# Regulator.net
KiCad netlist of a schematic drawn in Altium Designer
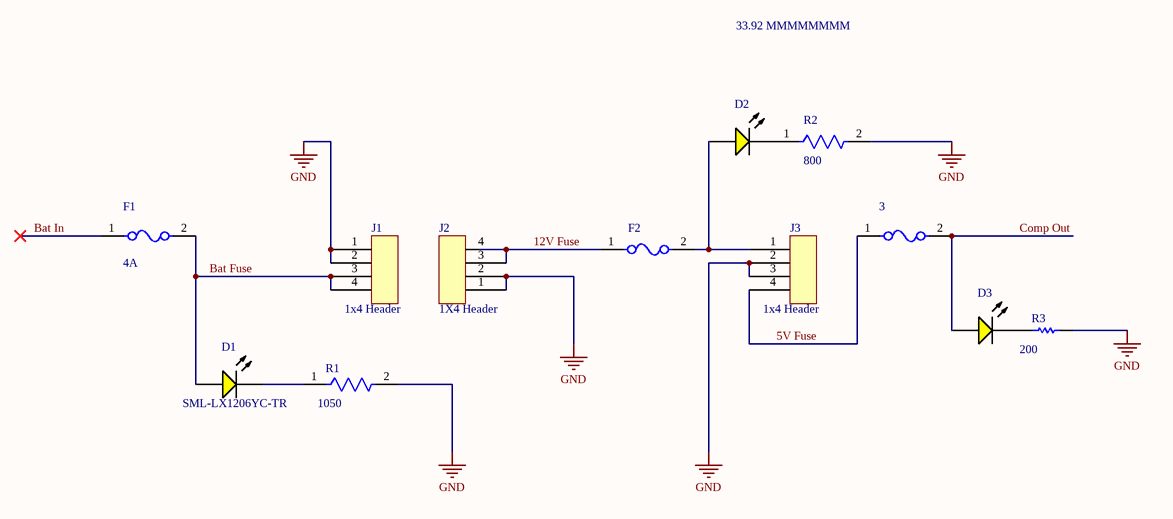
[diagram p0: Regulator.SchDoc]

(export (version "E")
  (design (tool "Eeschema 10.0.6"))
  (components
    (comp (ref "3")
      (value "5A")
      (footprint "FP-0469-MFG")
      (description "FUSE BOARD MOUNT 5A 32VDC 1206")
      (libsource (lib "Altium Content Vault") (part "5bcf9b9f640e542cf0359d10258e979"))
    )
    (comp (ref "D1")
      (value "SML-LX1206YC-TR")
      (footprint "LUMX-SML-LX1206YC-TR_V")
      (description "Yellow LED, Water Clear Len, 585 nm, 2.1 V, -40 to 85 degC, 2-Pin SMD, RoHS, Tape and Reel")
      (fields (field (name "MANUFACTURER") "Lumex"))
      (libsource (lib "Altium Content Vault") (part "LED-YELLOW-AK-2"))
    )
    (comp (ref "D2")
      (value "SML-LX1206YC-TR")
      (footprint "LUMX-SML-LX1206YC-TR_V")
      (description "Yellow LED, Water Clear Len, 585 nm, 2.1 V, -40 to 85 degC, 2-Pin SMD, RoHS, Tape and Reel")
      (fields (field (name "MANUFACTURER") "Lumex"))
      (libsource (lib "Altium Content Vault") (part "LED-YELLOW-AK-2"))
    )
    (comp (ref "D3")
      (value "SML-LX1206YC-TR")
      (footprint "LUMX-SML-LX1206YC-TR_V")
      (description "Yellow LED, Water Clear Len, 585 nm, 2.1 V, -40 to 85 degC, 2-Pin SMD, RoHS, Tape and Reel")
      (fields (field (name "MANUFACTURER") "Lumex"))
      (libsource (lib "Altium Content Vault") (part "LED-YELLOW-AK-2"))
    )
    (comp (ref "F1")
      (value "4A")
      (footprint "FP-0685T-IPC_B")
      (description "4A 63V AC 63V DC Fuse Board Mount (Cartridge Style Excluded) Surface Mount 1206 (3216 Metric)")
      (libsource (lib "Altium Content Vault") (part "5bcf9b9f640e542cf0359d10258e979"))
    )
    (comp (ref "F2")
      (value "3A")
      (footprint "FP-0466-MFG")
      (description "FUSE BOARD MNT 3A 32VAC/VDC 1206")
      (fields
        (field (name "OCTOPART") "https://octopart.com/0466003.nr-littelfuse-565175")
        (field (name "MANUFACTURER PART NUMBER") "0466003.NR")
      )
      (libsource (lib "Altium Content Vault") (part "5bcf9b9f640e542cf0359d10258e979"))
    )
    (comp (ref "J1")
      (value "1x4 Header")
      (footprint "1X4 HEADER")
      (description "CONN HEADER VERT 4POS 2.54MM")
      (fields
        (field (name "MANUFACTURER") "Würth Elektronik")
        (field (name "MANUFACTURER PART NUMBER") "61300411121")
      )
      (libsource (lib "URC_Lib") (part "1X4 Header"))
    )
    (comp (ref "J2")
      (value "1X4 Header")
      (footprint "1X4 HEADER")
      (description "CONN HEADER VERT 4POS 2.54MM")
      (fields
        (field (name "MANUFACTURER") "Würth Elektronik")
        (field (name "MANUFACTURER PART NUMBER") "61300411121")
      )
      (libsource (lib "") (part "1X4 Header_1"))
    )
    (comp (ref "J3")
      (value "1x4 Header")
      (footprint "1X4 HEADER")
      (description "CONN HEADER VERT 4POS 2.54MM")
      (fields
        (field (name "MANUFACTURER") "Würth Elektronik")
        (field (name "MANUFACTURER PART NUMBER") "61300411121")
      )
      (libsource (lib "URC_Lib") (part "1X4 Header"))
    )
    (comp (ref "R1")
      (value "1050")
      (footprint "FP-CR1206-IPC_B")
      (description "Thick Film Chip Resistors 1206 1.05kΩ 0.25W 1% 100ppm/°C")
      (fields (field (name "TOLERANCE") "1%"))
      (libsource (lib "Altium Content Vault") (part "1029c3af85768c4190bb7ad29bc67b5"))
    )
    (comp (ref "R2")
      (value "800")
      (footprint "FP-MCA1206-IPC_C")
      (description "Res MC Precision Thin Film 1206 800Ω 0.1% 0.25W ±25ppm/°C Molded Paper T/R")
      (fields (field (name "TOLERANCE") "0.1%"))
      (libsource (lib "Altium Content Vault") (part "1029c3af85768c4190bb7ad29bc67b5"))
    )
    (comp (ref "R3")
      (value "200")
      (footprint "RESC3216X70X50LL05T20")
      (fields (field (name "PART NUMBER") "ERJ-8GEYJ201V") (field (name "MANUFACTURER") "Panasonic"))
      (libsource (lib "Altium Content Vault") (part "RES"))
    )
  )
  (nets
    (net (code "1") (name "/5V Fuse") (class "Default")
      (node (ref "3") (pin "1") (pinfunction "1_1") (pintype "passive"))
      (node (ref "J3") (pin "4") (pinfunction "4_4") (pintype "passive"))
    )
    (net (code "2") (name "/12V Fuse") (class "Default")
      (node (ref "F2") (pin "1") (pinfunction "1_1") (pintype "passive"))
      (node (ref "J2") (pin "3") (pinfunction "3_3") (pintype "passive"))
      (node (ref "J2") (pin "4") (pinfunction "4_4") (pintype "passive"))
    )
    (net (code "3") (name "/Bat Fuse") (class "Default")
      (node (ref "D1") (pin "1") (pinfunction "A_1") (pintype "passive"))
      (node (ref "F1") (pin "2") (pinfunction "2_2") (pintype "passive"))
      (node (ref "J1") (pin "3") (pinfunction "3_3") (pintype "passive"))
      (node (ref "J1") (pin "4") (pinfunction "4_4") (pintype "passive"))
    )
    (net (code "4") (name "/Bat In") (class "Default")
      (node (ref "F1") (pin "1") (pinfunction "1_1") (pintype "passive+no_connect"))
    )
    (net (code "5") (name "/Comp Out") (class "Default")
      (node (ref "3") (pin "2") (pinfunction "2_2") (pintype "passive"))
      (node (ref "D3") (pin "1") (pinfunction "A_1") (pintype "passive"))
    )
    (net (code "6") (name "GND") (class "Default")
      (node (ref "J1") (pin "1") (pinfunction "1_1") (pintype "passive"))
      (node (ref "J1") (pin "2") (pinfunction "2_2") (pintype "passive"))
      (node (ref "J2") (pin "1") (pinfunction "1_1") (pintype "passive"))
      (node (ref "J2") (pin "2") (pinfunction "2_2") (pintype "passive"))
      (node (ref "J3") (pin "2") (pinfunction "2_2") (pintype "passive"))
      (node (ref "J3") (pin "3") (pinfunction "3_3") (pintype "passive"))
      (node (ref "R1") (pin "2") (pinfunction "2_2") (pintype "passive"))
      (node (ref "R2") (pin "2") (pinfunction "2_2") (pintype "passive"))
      (node (ref "R3") (pin "2") (pinfunction "2_2") (pintype "passive"))
    )
    (net (code "7") (name "Net-(D1-K)") (class "Default")
      (node (ref "D1") (pin "2") (pinfunction "K_2") (pintype "passive"))
      (node (ref "R1") (pin "1") (pinfunction "1_1") (pintype "passive"))
    )
    (net (code "8") (name "Net-(D2-A)") (class "Default")
      (node (ref "D2") (pin "1") (pinfunction "A_1") (pintype "passive"))
      (node (ref "F2") (pin "2") (pinfunction "2_2") (pintype "passive"))
      (node (ref "J3") (pin "1") (pinfunction "1_1") (pintype "passive"))
    )
    (net (code "9") (name "Net-(D2-K)") (class "Default")
      (node (ref "D2") (pin "2") (pinfunction "K_2") (pintype "passive"))
      (node (ref "R2") (pin "1") (pinfunction "1_1") (pintype "passive"))
    )
    (net (code "10") (name "Net-(D3-K)") (class "Default")
      (node (ref "D3") (pin "2") (pinfunction "K_2") (pintype "passive"))
      (node (ref "R3") (pin "1") (pinfunction "1_1") (pintype "passive"))
    )
  )
)
